# Power_Supplies.net
KiCad netlist of a schematic drawn in Altium Designer
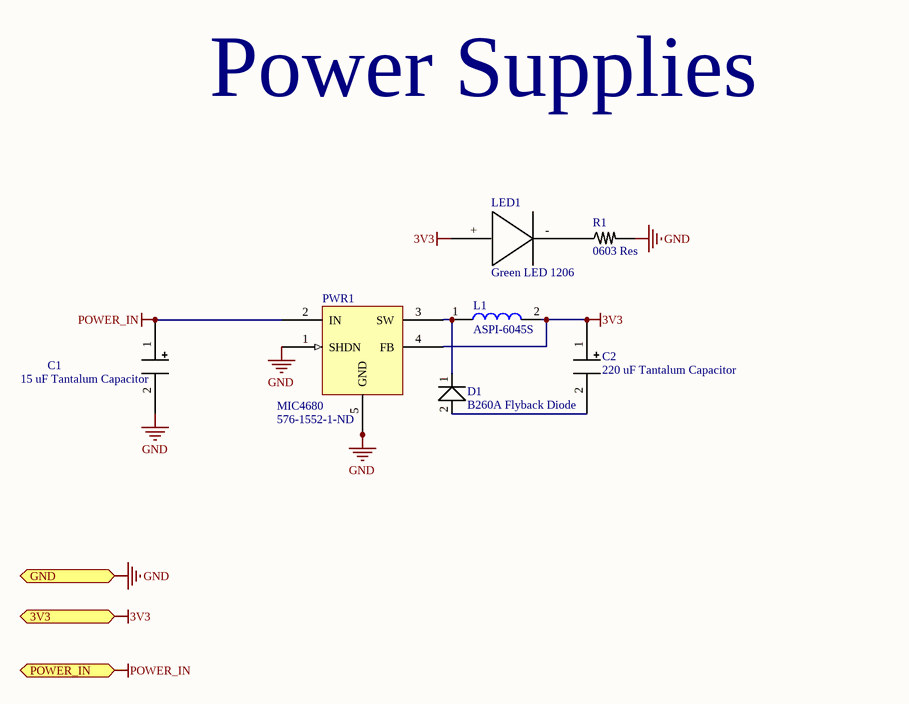
[diagram p0: Power_Supplies.SchDoc]

(export (version "E")
  (design (tool "Eeschema 10.0.6"))
  (components
    (comp (ref "C1")
      (value "15 uF Tantalum Capacitor")
      (footprint "1206 (POLAR)")
      (description "1206 Surface Mount Capacitor")
      (libsource (lib "CUBAJA") (part "15 uF Tantalum Capacitor"))
    )
    (comp (ref "C2")
      (value "220 uF Tantalum Capacitor")
      (footprint "1206 (POLAR)")
      (description "1206 Surface Mount Capacitor")
      (libsource (lib "CUBAJA") (part "15 uF Tantalum Capacitor"))
    )
    (comp (ref "D1")
      (value "B260A Flyback Diode")
      (footprint "DO-214AC")
      (libsource (lib "CUBAJA") (part "B260A Flyback Diode"))
    )
    (comp (ref "L1")
      (value "ASPI-6045S")
      (footprint "ASPI-6045")
      (description "68 uH 1.2A surface mount inductor")
      (libsource (lib "CUBAJA") (part "ASPI-6045S"))
    )
    (comp (ref "LED1")
      (value "Green LED 1206")
      (footprint "Cathode Mark 1206 led footprint")
      (description "Green surface mount LED")
      (libsource (lib "CUBAJA") (part "1206 Green LED"))
    )
    (comp (ref "PWR1")
      (value "MIC4680")
      (footprint "TJA1040")
      (description "3.3V Fixed Switching Regulator 1A")
      (fields (field (name "SUPPLIER PART NUMBER 1") "576-1552-1-ND"))
      (libsource (lib "CornellBajaLibrary") (part "MIC4680"))
    )
    (comp (ref "R1")
      (value "0603 Res")
      (footprint "0603/1608 SMD Resistor")
      (libsource (lib "CornellBajaLibrary") (part "0603 Res"))
    )
  )
  (nets
    (net (code "1") (name "3V3") (class "Default")
      (node (ref "C2") (pin "1") (pinfunction "1_1") (pintype "passive"))
      (node (ref "L1") (pin "2") (pinfunction "2_2") (pintype "passive"))
      (node (ref "LED1") (pin "+") (pintype "passive"))
      (node (ref "PWR1") (pin "4") (pinfunction "FB_4") (pintype "passive"))
    )
    (net (code "2") (name "GND") (class "Default")
      (node (ref "C1") (pin "2") (pinfunction "2_2") (pintype "passive"))
      (node (ref "PWR1") (pin "1") (pinfunction "SHDN_1") (pintype "input"))
      (node (ref "PWR1") (pin "5") (pinfunction "GND_5") (pintype "passive"))
      (node (ref "PWR1") (pin "6") (pinfunction "6_6") (pintype "passive"))
      (node (ref "PWR1") (pin "7") (pinfunction "7_7") (pintype "passive"))
      (node (ref "PWR1") (pin "8") (pinfunction "8_8") (pintype "passive"))
      (node (ref "R1") (pin "2") (pinfunction "2_2") (pintype "passive"))
    )
    (net (code "3") (name "Net-(C2-Pad2)") (class "Default")
      (node (ref "C2") (pin "2") (pinfunction "2_2") (pintype "passive"))
      (node (ref "D1") (pin "2") (pintype "passive"))
    )
    (net (code "4") (name "Net-(LED1-Pad-)") (class "Default")
      (node (ref "LED1") (pin "-") (pintype "passive"))
      (node (ref "R1") (pin "1") (pinfunction "1_1") (pintype "passive"))
    )
    (net (code "5") (name "Net-(PWR1-SW)") (class "Default")
      (node (ref "D1") (pin "1") (pintype "passive"))
      (node (ref "L1") (pin "1") (pinfunction "1_1") (pintype "passive"))
      (node (ref "PWR1") (pin "3") (pinfunction "SW_3") (pintype "passive"))
    )
    (net (code "6") (name "POWER_IN") (class "Default")
      (node (ref "C1") (pin "1") (pinfunction "1_1") (pintype "passive"))
      (node (ref "PWR1") (pin "2") (pinfunction "IN_2") (pintype "passive"))
    )
  )
)
